# Debug_Module.net
KiCad netlist of a schematic drawn in EAGLE
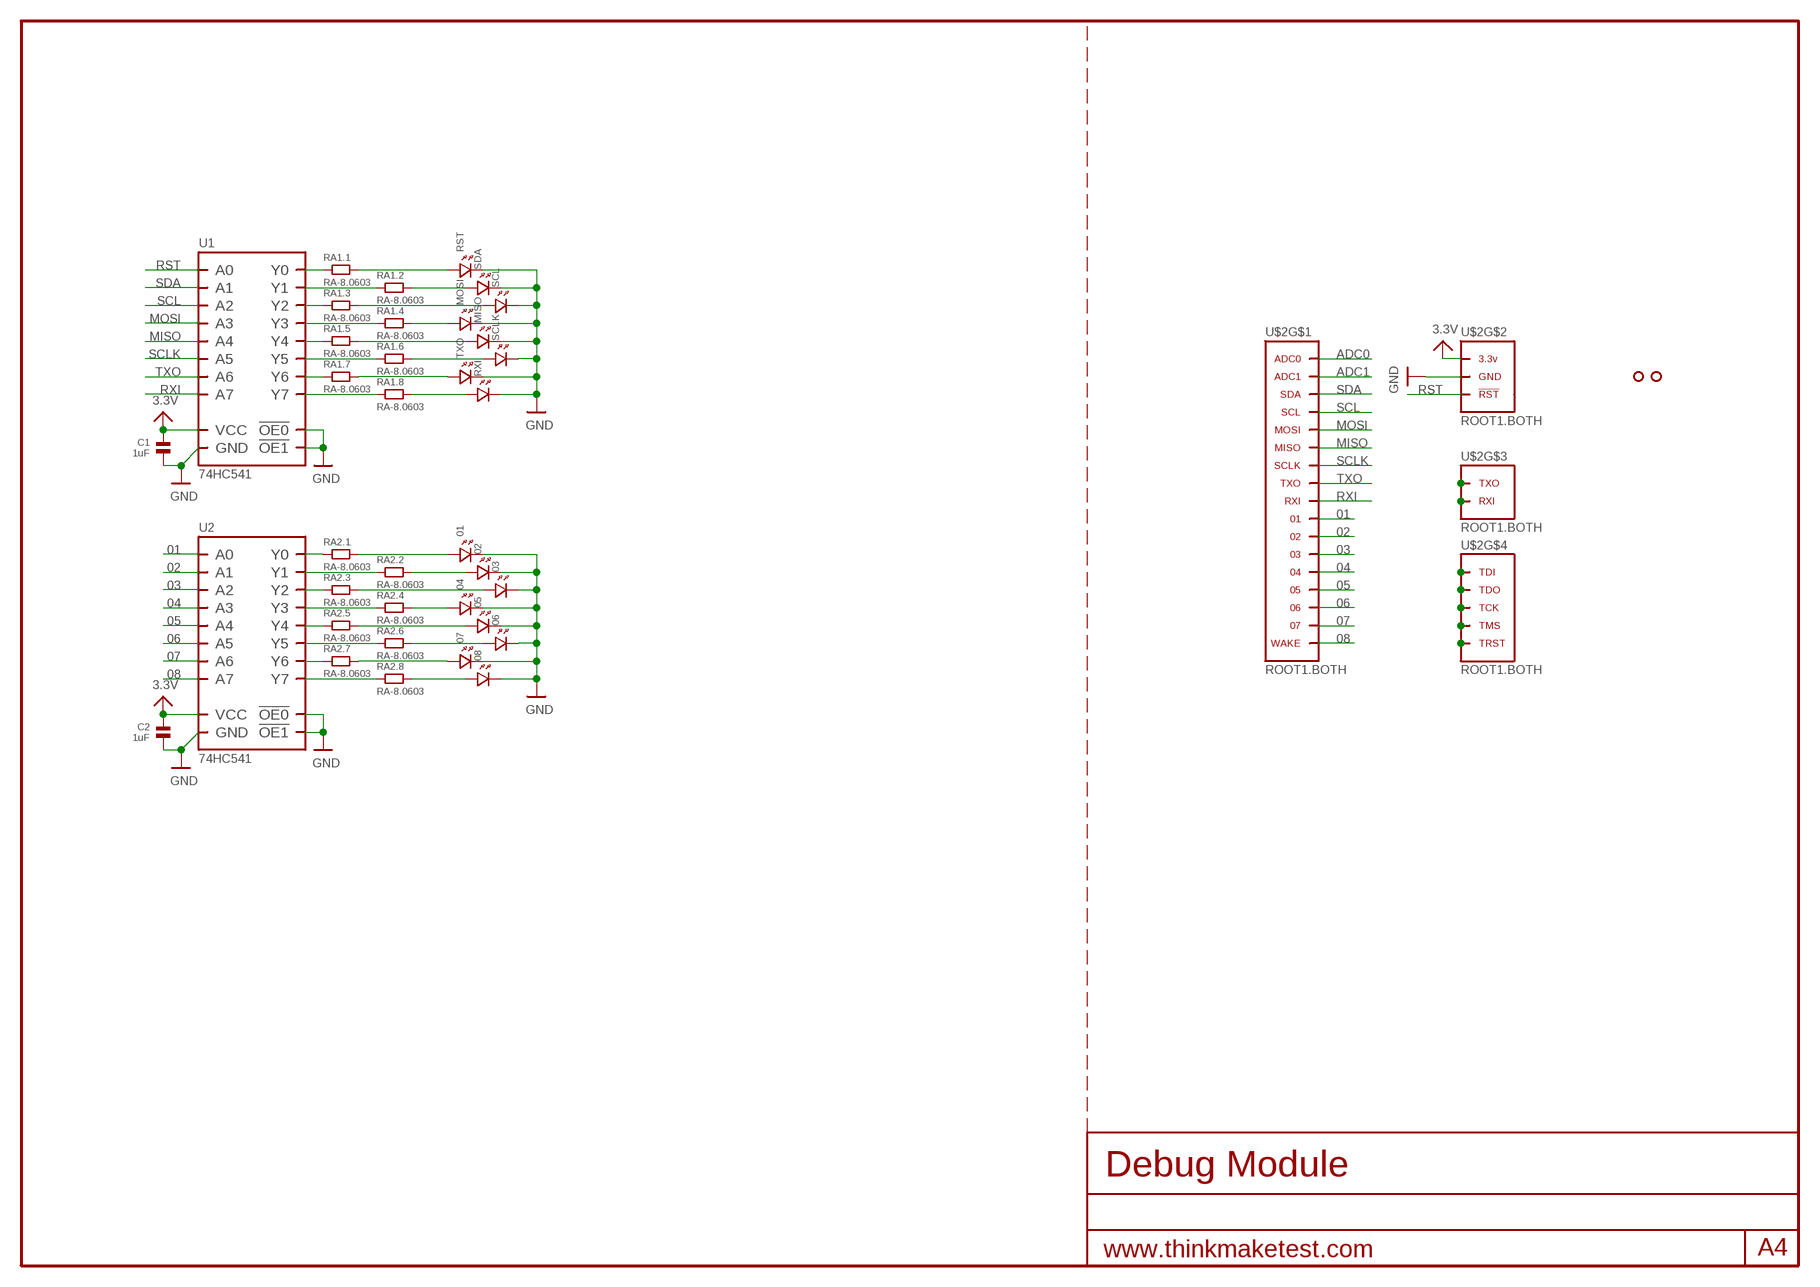
[diagram p0: schematic, sheet 1]

(export (version "E")
  (design (tool "Eeschema 10.0.6"))
  (components
    (comp (ref "01")
      (value "LED.0603")
      (footprint "eagle-import:0603.LED")
      (libsource (lib "eagle-import") (part "LED.0603"))
    )
    (comp (ref "02")
      (value "LED.0603")
      (footprint "eagle-import:0603.LED")
      (libsource (lib "eagle-import") (part "LED.0603"))
    )
    (comp (ref "03")
      (value "LED.0603")
      (footprint "eagle-import:0603.LED")
      (libsource (lib "eagle-import") (part "LED.0603"))
    )
    (comp (ref "04")
      (value "LED.0603")
      (footprint "eagle-import:0603.LED")
      (libsource (lib "eagle-import") (part "LED.0603"))
    )
    (comp (ref "05")
      (value "LED.0603")
      (footprint "eagle-import:0603.LED")
      (libsource (lib "eagle-import") (part "LED.0603"))
    )
    (comp (ref "06")
      (value "LED.0603")
      (footprint "eagle-import:0603.LED")
      (libsource (lib "eagle-import") (part "LED.0603"))
    )
    (comp (ref "07")
      (value "LED.0603")
      (footprint "eagle-import:0603.LED")
      (libsource (lib "eagle-import") (part "LED.0603"))
    )
    (comp (ref "08")
      (value "LED.0603")
      (footprint "eagle-import:0603.LED")
      (libsource (lib "eagle-import") (part "LED.0603"))
    )
    (comp (ref "C1")
      (value "1uF")
      (footprint "eagle-import:0603")
      (libsource (lib "eagle-import") (part "CAPACITOR.0603"))
    )
    (comp (ref "C2")
      (value "1uF")
      (footprint "eagle-import:0603")
      (libsource (lib "eagle-import") (part "CAPACITOR.0603"))
    )
    (comp (ref "MISO")
      (value "LED.0603")
      (footprint "eagle-import:0603.LED")
      (libsource (lib "eagle-import") (part "LED.0603"))
    )
    (comp (ref "MOSI")
      (value "LED.0603")
      (footprint "eagle-import:0603.LED")
      (libsource (lib "eagle-import") (part "LED.0603"))
    )
    (comp (ref "RA1")
      (value "RA-8.0603")
      (footprint "eagle-import:0603.8.C")
      (libsource (lib "eagle-import") (part "RA-8.0603"))
    )
    (comp (ref "RA2")
      (value "RA-8.0603")
      (footprint "eagle-import:0603.8.C")
      (libsource (lib "eagle-import") (part "RA-8.0603"))
    )
    (comp (ref "RST")
      (value "LED.0603")
      (footprint "eagle-import:0603.LED")
      (libsource (lib "eagle-import") (part "LED.0603"))
    )
    (comp (ref "RXI")
      (value "LED.0603")
      (footprint "eagle-import:0603.LED")
      (libsource (lib "eagle-import") (part "LED.0603"))
    )
    (comp (ref "SCL")
      (value "LED.0603")
      (footprint "eagle-import:0603.LED")
      (libsource (lib "eagle-import") (part "LED.0603"))
    )
    (comp (ref "SCLK")
      (value "LED.0603")
      (footprint "eagle-import:0603.LED")
      (libsource (lib "eagle-import") (part "LED.0603"))
    )
    (comp (ref "SDA")
      (value "LED.0603")
      (footprint "eagle-import:0603.LED")
      (libsource (lib "eagle-import") (part "LED.0603"))
    )
    (comp (ref "TXO")
      (value "LED.0603")
      (footprint "eagle-import:0603.LED")
      (libsource (lib "eagle-import") (part "LED.0603"))
    )
    (comp (ref "U$2")
      (value "ROOT1.BOTH")
      (footprint "eagle-import:ROOT1.BOTH")
      (libsource (lib "eagle-import") (part "ROOT1.BOTH"))
    )
    (comp (ref "U$3")
      (value "HOLE.2MM")
      (footprint "eagle-import:2MM")
      (libsource (lib "eagle-import") (part "HOLE.2MM"))
    )
    (comp (ref "U$4")
      (value "HOLE.2MM")
      (footprint "eagle-import:2MM")
      (libsource (lib "eagle-import") (part "HOLE.2MM"))
    )
    (comp (ref "U1")
      (value "74HC541")
      (footprint "eagle-import:DHVQFN20")
      (libsource (lib "eagle-import") (part "74HC541"))
    )
    (comp (ref "U2")
      (value "74HC541")
      (footprint "eagle-import:DHVQFN20")
      (libsource (lib "eagle-import") (part "74HC541"))
    )
  )
  (nets
    (net (code "1") (name "/01") (class "Default")
      (node (ref "U$2") (pin "01") (pinfunction "01_01") (pintype "bidirectional"))
      (node (ref "U$2") (pin "01@1") (pinfunction "01_01@1") (pintype "bidirectional"))
      (node (ref "U$2") (pin "01@VIA") (pinfunction "01_01@VIA") (pintype "bidirectional"))
      (node (ref "U2") (pin "2") (pinfunction "A0_2") (pintype "bidirectional"))
    )
    (net (code "2") (name "/02") (class "Default")
      (node (ref "U$2") (pin "02") (pinfunction "02_02") (pintype "bidirectional"))
      (node (ref "U$2") (pin "02@1") (pinfunction "02_02@1") (pintype "bidirectional"))
      (node (ref "U$2") (pin "02@VIA") (pinfunction "02_02@VIA") (pintype "bidirectional"))
      (node (ref "U2") (pin "3") (pinfunction "A1_3") (pintype "bidirectional"))
    )
    (net (code "3") (name "/03") (class "Default")
      (node (ref "U$2") (pin "03") (pinfunction "03_03") (pintype "bidirectional"))
      (node (ref "U$2") (pin "03@1") (pinfunction "03_03@1") (pintype "bidirectional"))
      (node (ref "U$2") (pin "03@VIA") (pinfunction "03_03@VIA") (pintype "bidirectional"))
      (node (ref "U2") (pin "4") (pinfunction "A2_4") (pintype "bidirectional"))
    )
    (net (code "4") (name "/04") (class "Default")
      (node (ref "U$2") (pin "04") (pinfunction "04_04") (pintype "bidirectional"))
      (node (ref "U$2") (pin "04@1") (pinfunction "04_04@1") (pintype "bidirectional"))
      (node (ref "U$2") (pin "04@VIA") (pinfunction "04_04@VIA") (pintype "bidirectional"))
      (node (ref "U2") (pin "5") (pinfunction "A3_5") (pintype "bidirectional"))
    )
    (net (code "5") (name "/05") (class "Default")
      (node (ref "U$2") (pin "05") (pinfunction "05_05") (pintype "bidirectional"))
      (node (ref "U$2") (pin "05@1") (pinfunction "05_05@1") (pintype "bidirectional"))
      (node (ref "U$2") (pin "05@VIA") (pinfunction "05_05@VIA") (pintype "bidirectional"))
      (node (ref "U2") (pin "6") (pinfunction "A4_6") (pintype "bidirectional"))
    )
    (net (code "6") (name "/06") (class "Default")
      (node (ref "U$2") (pin "06") (pinfunction "06_06") (pintype "bidirectional"))
      (node (ref "U$2") (pin "06@1") (pinfunction "06_06@1") (pintype "bidirectional"))
      (node (ref "U$2") (pin "06@VIA") (pinfunction "06_06@VIA") (pintype "bidirectional"))
      (node (ref "U2") (pin "7") (pinfunction "A5_7") (pintype "bidirectional"))
    )
    (net (code "7") (name "/07") (class "Default")
      (node (ref "U$2") (pin "07") (pinfunction "07_07") (pintype "bidirectional"))
      (node (ref "U$2") (pin "07@1") (pinfunction "07_07@1") (pintype "bidirectional"))
      (node (ref "U$2") (pin "07@VIA") (pinfunction "07_07@VIA") (pintype "bidirectional"))
      (node (ref "U2") (pin "8") (pinfunction "A6_8") (pintype "bidirectional"))
    )
    (net (code "8") (name "/08") (class "Default")
      (node (ref "U$2") (pin "WAKE") (pinfunction "WAKE_WAKE") (pintype "bidirectional"))
      (node (ref "U$2") (pin "WAKE@1") (pinfunction "WAKE_WAKE@1") (pintype "bidirectional"))
      (node (ref "U$2") (pin "WAKE@VIA") (pinfunction "WAKE_WAKE@VIA") (pintype "bidirectional"))
      (node (ref "U2") (pin "9") (pinfunction "A7_9") (pintype "bidirectional"))
    )
    (net (code "9") (name "/ADC0") (class "Default")
      (node (ref "U$2") (pin "ADC0") (pinfunction "ADC0_ADC0") (pintype "bidirectional"))
      (node (ref "U$2") (pin "ADC0@1") (pinfunction "ADC0_ADC0@1") (pintype "bidirectional"))
      (node (ref "U$2") (pin "ADC0@VIA") (pinfunction "ADC0_ADC0@VIA") (pintype "bidirectional"))
    )
    (net (code "10") (name "/ADC1") (class "Default")
      (node (ref "U$2") (pin "ADC1") (pinfunction "ADC1_ADC1") (pintype "bidirectional"))
      (node (ref "U$2") (pin "ADC1@1") (pinfunction "ADC1_ADC1@1") (pintype "bidirectional"))
      (node (ref "U$2") (pin "ADC1@VIA") (pinfunction "ADC1_ADC1@VIA") (pintype "bidirectional"))
    )
    (net (code "11") (name "/MISO") (class "Default")
      (node (ref "U$2") (pin "MISO") (pinfunction "MISO_MISO") (pintype "bidirectional"))
      (node (ref "U$2") (pin "MISO@1") (pinfunction "MISO_MISO@1") (pintype "bidirectional"))
      (node (ref "U$2") (pin "MISO@VIA") (pinfunction "MISO_MISO@VIA") (pintype "bidirectional"))
      (node (ref "U1") (pin "6") (pinfunction "A4_6") (pintype "bidirectional"))
    )
    (net (code "12") (name "/MOSI") (class "Default")
      (node (ref "U$2") (pin "MOSI") (pinfunction "MOSI_MOSI") (pintype "bidirectional"))
      (node (ref "U$2") (pin "MOSI@1") (pinfunction "MOSI_MOSI@1") (pintype "bidirectional"))
      (node (ref "U$2") (pin "MOSI@VIA") (pinfunction "MOSI_MOSI@VIA") (pintype "bidirectional"))
      (node (ref "U1") (pin "5") (pinfunction "A3_5") (pintype "bidirectional"))
    )
    (net (code "13") (name "/RST") (class "Default")
      (node (ref "U$2") (pin "RST") (pinfunction "~{RST}_RST") (pintype "bidirectional"))
      (node (ref "U$2") (pin "RST@1") (pinfunction "~{RST}_RST@1") (pintype "bidirectional"))
      (node (ref "U$2") (pin "RST@VIA") (pinfunction "~{RST}_RST@VIA") (pintype "bidirectional"))
      (node (ref "U1") (pin "2") (pinfunction "A0_2") (pintype "bidirectional"))
    )
    (net (code "14") (name "/RXI") (class "Default")
      (node (ref "U$2") (pin "RXI") (pinfunction "RXI_RXI") (pintype "bidirectional"))
      (node (ref "U$2") (pin "RXI@1") (pinfunction "RXI_RXI@1") (pintype "bidirectional"))
      (node (ref "U$2") (pin "RXI@VIA") (pinfunction "RXI_RXI@VIA") (pintype "bidirectional"))
      (node (ref "U1") (pin "9") (pinfunction "A7_9") (pintype "bidirectional"))
    )
    (net (code "15") (name "/SCL") (class "Default")
      (node (ref "U$2") (pin "SCL") (pinfunction "SCL_SCL") (pintype "bidirectional"))
      (node (ref "U$2") (pin "SCL@1") (pinfunction "SCL_SCL@1") (pintype "bidirectional"))
      (node (ref "U$2") (pin "SCL@VIA") (pinfunction "SCL_SCL@VIA") (pintype "bidirectional"))
      (node (ref "U1") (pin "4") (pinfunction "A2_4") (pintype "bidirectional"))
    )
    (net (code "16") (name "/SCLK") (class "Default")
      (node (ref "U$2") (pin "SCLK") (pinfunction "SCLK_SCLK") (pintype "bidirectional"))
      (node (ref "U$2") (pin "SCLK@1") (pinfunction "SCLK_SCLK@1") (pintype "bidirectional"))
      (node (ref "U$2") (pin "SCLK@VIA") (pinfunction "SCLK_SCLK@VIA") (pintype "bidirectional"))
      (node (ref "U1") (pin "7") (pinfunction "A5_7") (pintype "bidirectional"))
    )
    (net (code "17") (name "/SDA") (class "Default")
      (node (ref "U$2") (pin "SDA") (pinfunction "SDA_SDA") (pintype "bidirectional"))
      (node (ref "U$2") (pin "SDA@1") (pinfunction "SDA_SDA@1") (pintype "bidirectional"))
      (node (ref "U$2") (pin "SDA@VIA") (pinfunction "SDA_SDA@VIA") (pintype "bidirectional"))
      (node (ref "U1") (pin "3") (pinfunction "A1_3") (pintype "bidirectional"))
    )
    (net (code "18") (name "/TXO") (class "Default")
      (node (ref "U$2") (pin "TXO") (pinfunction "TXO_TXO") (pintype "bidirectional"))
      (node (ref "U$2") (pin "TXO@1") (pinfunction "TXO_TXO@1") (pintype "bidirectional"))
      (node (ref "U$2") (pin "TXO@VIA") (pinfunction "TXO_TXO@VIA") (pintype "bidirectional"))
      (node (ref "U1") (pin "8") (pinfunction "A6_8") (pintype "bidirectional"))
    )
    (net (code "19") (name "3.3V") (class "Default")
      (node (ref "C1") (pin "1") (pinfunction "1_1") (pintype "bidirectional"))
      (node (ref "C2") (pin "1") (pinfunction "1_1") (pintype "bidirectional"))
      (node (ref "U$2") (pin "3.3V@1") (pinfunction "3.3V_3.3V@1") (pintype "bidirectional"))
      (node (ref "U$2") (pin "3.3V@10") (pinfunction "3.3V_3.3V@10") (pintype "bidirectional"))
      (node (ref "U$2") (pin "3.3V@11") (pinfunction "3.3V_3.3V@11") (pintype "bidirectional"))
      (node (ref "U$2") (pin "3.3V@12") (pinfunction "3.3V_3.3V@12") (pintype "bidirectional"))
      (node (ref "U$2") (pin "3.3V@13") (pinfunction "3.3V_3.3V@13") (pintype "bidirectional"))
      (node (ref "U$2") (pin "3.3V@14") (pinfunction "3.3V_3.3V@14") (pintype "bidirectional"))
      (node (ref "U$2") (pin "3.3V@15") (pinfunction "3.3V_3.3V@15") (pintype "bidirectional"))
      (node (ref "U$2") (pin "3.3V@16") (pinfunction "3.3V_3.3V@16") (pintype "bidirectional"))
      (node (ref "U$2") (pin "3.3V@17") (pinfunction "3.3V_3.3V@17") (pintype "bidirectional"))
      (node (ref "U$2") (pin "3.3V@18") (pinfunction "3.3V_3.3V@18") (pintype "bidirectional"))
      (node (ref "U$2") (pin "3.3V@19") (pinfunction "3.3V_3.3V@19") (pintype "bidirectional"))
      (node (ref "U$2") (pin "3.3V@2") (pinfunction "3.3V_3.3V@2") (pintype "bidirectional"))
      (node (ref "U$2") (pin "3.3V@20") (pinfunction "3.3V_3.3V@20") (pintype "bidirectional"))
      (node (ref "U$2") (pin "3.3V@21") (pinfunction "3.3V_3.3V@21") (pintype "bidirectional"))
      (node (ref "U$2") (pin "3.3V@22") (pinfunction "3.3V_3.3V@22") (pintype "bidirectional"))
      (node (ref "U$2") (pin "3.3V@23") (pinfunction "3.3V_3.3V@23") (pintype "bidirectional"))
      (node (ref "U$2") (pin "3.3V@24") (pinfunction "3.3V_3.3V@24") (pintype "bidirectional"))
      (node (ref "U$2") (pin "3.3V@3") (pinfunction "3.3V_3.3V@3") (pintype "bidirectional"))
      (node (ref "U$2") (pin "3.3V@4") (pinfunction "3.3V_3.3V@4") (pintype "bidirectional"))
      (node (ref "U$2") (pin "3.3V@5") (pinfunction "3.3V_3.3V@5") (pintype "bidirectional"))
      (node (ref "U$2") (pin "3.3V@6") (pinfunction "3.3V_3.3V@6") (pintype "bidirectional"))
      (node (ref "U$2") (pin "3.3V@7") (pinfunction "3.3V_3.3V@7") (pintype "bidirectional"))
      (node (ref "U$2") (pin "3.3V@8") (pinfunction "3.3V_3.3V@8") (pintype "bidirectional"))
      (node (ref "U$2") (pin "3.3V@9") (pinfunction "3.3V_3.3V@9") (pintype "bidirectional"))
      (node (ref "U$2") (pin "3.3V@VIA") (pinfunction "3.3V_3.3V@VIA") (pintype "bidirectional"))
      (node (ref "U1") (pin "20") (pinfunction "VCC_20") (pintype "bidirectional"))
      (node (ref "U2") (pin "20") (pinfunction "VCC_20") (pintype "bidirectional"))
    )
    (net (code "20") (name "GND") (class "Default")
      (node (ref "01") (pin "P$2") (pinfunction "2_P$2") (pintype "bidirectional"))
      (node (ref "02") (pin "P$2") (pinfunction "2_P$2") (pintype "bidirectional"))
      (node (ref "03") (pin "P$2") (pinfunction "2_P$2") (pintype "bidirectional"))
      (node (ref "04") (pin "P$2") (pinfunction "2_P$2") (pintype "bidirectional"))
      (node (ref "05") (pin "P$2") (pinfunction "2_P$2") (pintype "bidirectional"))
      (node (ref "06") (pin "P$2") (pinfunction "2_P$2") (pintype "bidirectional"))
      (node (ref "07") (pin "P$2") (pinfunction "2_P$2") (pintype "bidirectional"))
      (node (ref "08") (pin "P$2") (pinfunction "2_P$2") (pintype "bidirectional"))
      (node (ref "C1") (pin "2") (pinfunction "2_2") (pintype "bidirectional"))
      (node (ref "C2") (pin "2") (pinfunction "2_2") (pintype "bidirectional"))
      (node (ref "MISO") (pin "P$2") (pinfunction "2_P$2") (pintype "bidirectional"))
      (node (ref "MOSI") (pin "P$2") (pinfunction "2_P$2") (pintype "bidirectional"))
      (node (ref "RST") (pin "P$2") (pinfunction "2_P$2") (pintype "bidirectional"))
      (node (ref "RXI") (pin "P$2") (pinfunction "2_P$2") (pintype "bidirectional"))
      (node (ref "SCL") (pin "P$2") (pinfunction "2_P$2") (pintype "bidirectional"))
      (node (ref "SCLK") (pin "P$2") (pinfunction "2_P$2") (pintype "bidirectional"))
      (node (ref "SDA") (pin "P$2") (pinfunction "2_P$2") (pintype "bidirectional"))
      (node (ref "TXO") (pin "P$2") (pinfunction "2_P$2") (pintype "bidirectional"))
      (node (ref "U$2") (pin "GND@1") (pinfunction "GND_GND@1") (pintype "bidirectional"))
      (node (ref "U$2") (pin "GND@10") (pinfunction "GND_GND@10") (pintype "bidirectional"))
      (node (ref "U$2") (pin "GND@11") (pinfunction "GND_GND@11") (pintype "bidirectional"))
      (node (ref "U$2") (pin "GND@12") (pinfunction "GND_GND@12") (pintype "bidirectional"))
      (node (ref "U$2") (pin "GND@13") (pinfunction "GND_GND@13") (pintype "bidirectional"))
      (node (ref "U$2") (pin "GND@14") (pinfunction "GND_GND@14") (pintype "bidirectional"))
      (node (ref "U$2") (pin "GND@15") (pinfunction "GND_GND@15") (pintype "bidirectional"))
      (node (ref "U$2") (pin "GND@16") (pinfunction "GND_GND@16") (pintype "bidirectional"))
      (node (ref "U$2") (pin "GND@17") (pinfunction "GND_GND@17") (pintype "bidirectional"))
      (node (ref "U$2") (pin "GND@18") (pinfunction "GND_GND@18") (pintype "bidirectional"))
      (node (ref "U$2") (pin "GND@19") (pinfunction "GND_GND@19") (pintype "bidirectional"))
      (node (ref "U$2") (pin "GND@2") (pinfunction "GND_GND@2") (pintype "bidirectional"))
      (node (ref "U$2") (pin "GND@20") (pinfunction "GND_GND@20") (pintype "bidirectional"))
      (node (ref "U$2") (pin "GND@21") (pinfunction "GND_GND@21") (pintype "bidirectional"))
      (node (ref "U$2") (pin "GND@22") (pinfunction "GND_GND@22") (pintype "bidirectional"))
      (node (ref "U$2") (pin "GND@23") (pinfunction "GND_GND@23") (pintype "bidirectional"))
      (node (ref "U$2") (pin "GND@24") (pinfunction "GND_GND@24") (pintype "bidirectional"))
      (node (ref "U$2") (pin "GND@25") (pinfunction "GND_GND@25") (pintype "bidirectional"))
      (node (ref "U$2") (pin "GND@26") (pinfunction "GND_GND@26") (pintype "bidirectional"))
      (node (ref "U$2") (pin "GND@3") (pinfunction "GND_GND@3") (pintype "bidirectional"))
      (node (ref "U$2") (pin "GND@4") (pinfunction "GND_GND@4") (pintype "bidirectional"))
      (node (ref "U$2") (pin "GND@5") (pinfunction "GND_GND@5") (pintype "bidirectional"))
      (node (ref "U$2") (pin "GND@6") (pinfunction "GND_GND@6") (pintype "bidirectional"))
      (node (ref "U$2") (pin "GND@7") (pinfunction "GND_GND@7") (pintype "bidirectional"))
      (node (ref "U$2") (pin "GND@8") (pinfunction "GND_GND@8") (pintype "bidirectional"))
      (node (ref "U$2") (pin "GND@9") (pinfunction "GND_GND@9") (pintype "bidirectional"))
      (node (ref "U$2") (pin "GND@VIA") (pinfunction "GND_GND@VIA") (pintype "bidirectional"))
      (node (ref "U1") (pin "1") (pinfunction "~{OE0}_1") (pintype "bidirectional"))
      (node (ref "U1") (pin "10") (pinfunction "GND_10") (pintype "bidirectional"))
      (node (ref "U1") (pin "19") (pinfunction "~{OE1}_19") (pintype "bidirectional"))
      (node (ref "U1") (pin "PAD") (pinfunction "GND_PAD") (pintype "bidirectional"))
      (node (ref "U2") (pin "1") (pinfunction "~{OE0}_1") (pintype "bidirectional"))
      (node (ref "U2") (pin "10") (pinfunction "GND_10") (pintype "bidirectional"))
      (node (ref "U2") (pin "19") (pinfunction "~{OE1}_19") (pintype "bidirectional"))
      (node (ref "U2") (pin "PAD") (pinfunction "GND_PAD") (pintype "bidirectional"))
    )
    (net (code "21") (name "Net-(01-1)") (class "Default")
      (node (ref "01") (pin "P$1") (pinfunction "1_P$1") (pintype "bidirectional"))
      (node (ref "RA2") (pin "2") (pinfunction "2_2") (pintype "bidirectional"))
    )
    (net (code "22") (name "Net-(02-1)") (class "Default")
      (node (ref "02") (pin "P$1") (pinfunction "1_P$1") (pintype "bidirectional"))
      (node (ref "RA2") (pin "4") (pinfunction "2_4") (pintype "bidirectional"))
    )
    (net (code "23") (name "Net-(03-1)") (class "Default")
      (node (ref "03") (pin "P$1") (pinfunction "1_P$1") (pintype "bidirectional"))
      (node (ref "RA2") (pin "6") (pinfunction "2_6") (pintype "bidirectional"))
    )
    (net (code "24") (name "Net-(04-1)") (class "Default")
      (node (ref "04") (pin "P$1") (pinfunction "1_P$1") (pintype "bidirectional"))
      (node (ref "RA2") (pin "8") (pinfunction "2_8") (pintype "bidirectional"))
    )
    (net (code "25") (name "Net-(05-1)") (class "Default")
      (node (ref "05") (pin "P$1") (pinfunction "1_P$1") (pintype "bidirectional"))
      (node (ref "RA2") (pin "10") (pinfunction "2_10") (pintype "bidirectional"))
    )
    (net (code "26") (name "Net-(06-1)") (class "Default")
      (node (ref "06") (pin "P$1") (pinfunction "1_P$1") (pintype "bidirectional"))
      (node (ref "RA2") (pin "12") (pinfunction "2_12") (pintype "bidirectional"))
    )
    (net (code "27") (name "Net-(07-1)") (class "Default")
      (node (ref "07") (pin "P$1") (pinfunction "1_P$1") (pintype "bidirectional"))
      (node (ref "RA2") (pin "14") (pinfunction "2_14") (pintype "bidirectional"))
    )
    (net (code "28") (name "Net-(08-1)") (class "Default")
      (node (ref "08") (pin "P$1") (pinfunction "1_P$1") (pintype "bidirectional"))
      (node (ref "RA2") (pin "16") (pinfunction "2_16") (pintype "bidirectional"))
    )
    (net (code "29") (name "Net-(MISO-1)") (class "Default")
      (node (ref "MISO") (pin "P$1") (pinfunction "1_P$1") (pintype "bidirectional"))
      (node (ref "RA1") (pin "10") (pinfunction "2_10") (pintype "bidirectional"))
    )
    (net (code "30") (name "Net-(MOSI-1)") (class "Default")
      (node (ref "MOSI") (pin "P$1") (pinfunction "1_P$1") (pintype "bidirectional"))
      (node (ref "RA1") (pin "8") (pinfunction "2_8") (pintype "bidirectional"))
    )
    (net (code "31") (name "Net-(RA1B-1)") (class "Default")
      (node (ref "RA1") (pin "3") (pinfunction "1_3") (pintype "bidirectional"))
      (node (ref "U1") (pin "17") (pinfunction "Y1_17") (pintype "bidirectional"))
    )
    (net (code "32") (name "Net-(RA1B-2)") (class "Default")
      (node (ref "RA1") (pin "4") (pinfunction "2_4") (pintype "bidirectional"))
      (node (ref "SDA") (pin "P$1") (pinfunction "1_P$1") (pintype "bidirectional"))
    )
    (net (code "33") (name "Net-(RA1C-1)") (class "Default")
      (node (ref "RA1") (pin "5") (pinfunction "1_5") (pintype "bidirectional"))
      (node (ref "U1") (pin "16") (pinfunction "Y2_16") (pintype "bidirectional"))
    )
    (net (code "34") (name "Net-(RA1C-2)") (class "Default")
      (node (ref "RA1") (pin "6") (pinfunction "2_6") (pintype "bidirectional"))
      (node (ref "SCL") (pin "P$1") (pinfunction "1_P$1") (pintype "bidirectional"))
    )
    (net (code "35") (name "Net-(RA1D-1)") (class "Default")
      (node (ref "RA1") (pin "7") (pinfunction "1_7") (pintype "bidirectional"))
      (node (ref "U1") (pin "15") (pinfunction "Y3_15") (pintype "bidirectional"))
    )
    (net (code "36") (name "Net-(RA1E-1)") (class "Default")
      (node (ref "RA1") (pin "9") (pinfunction "1_9") (pintype "bidirectional"))
      (node (ref "U1") (pin "14") (pinfunction "Y4_14") (pintype "bidirectional"))
    )
    (net (code "37") (name "Net-(RA1F-1)") (class "Default")
      (node (ref "RA1") (pin "11") (pinfunction "1_11") (pintype "bidirectional"))
      (node (ref "U1") (pin "13") (pinfunction "Y5_13") (pintype "bidirectional"))
    )
    (net (code "38") (name "Net-(RA1F-2)") (class "Default")
      (node (ref "RA1") (pin "12") (pinfunction "2_12") (pintype "bidirectional"))
      (node (ref "SCLK") (pin "P$1") (pinfunction "1_P$1") (pintype "bidirectional"))
    )
    (net (code "39") (name "Net-(RA1G-1)") (class "Default")
      (node (ref "RA1") (pin "13") (pinfunction "1_13") (pintype "bidirectional"))
      (node (ref "U1") (pin "12") (pinfunction "Y6_12") (pintype "bidirectional"))
    )
    (net (code "40") (name "Net-(RA1G-2)") (class "Default")
      (node (ref "RA1") (pin "14") (pinfunction "2_14") (pintype "bidirectional"))
      (node (ref "TXO") (pin "P$1") (pinfunction "1_P$1") (pintype "bidirectional"))
    )
    (net (code "41") (name "Net-(RA1H-1)") (class "Default")
      (node (ref "RA1") (pin "15") (pinfunction "1_15") (pintype "bidirectional"))
      (node (ref "U1") (pin "11") (pinfunction "Y7_11") (pintype "bidirectional"))
    )
    (net (code "42") (name "Net-(RA1H-2)") (class "Default")
      (node (ref "RA1") (pin "16") (pinfunction "2_16") (pintype "bidirectional"))
      (node (ref "RXI") (pin "P$1") (pinfunction "1_P$1") (pintype "bidirectional"))
    )
    (net (code "43") (name "Net-(RA2B-1)") (class "Default")
      (node (ref "RA2") (pin "3") (pinfunction "1_3") (pintype "bidirectional"))
      (node (ref "U2") (pin "17") (pinfunction "Y1_17") (pintype "bidirectional"))
    )
    (net (code "44") (name "Net-(RA2C-1)") (class "Default")
      (node (ref "RA2") (pin "5") (pinfunction "1_5") (pintype "bidirectional"))
      (node (ref "U2") (pin "16") (pinfunction "Y2_16") (pintype "bidirectional"))
    )
    (net (code "45") (name "Net-(RA2D-1)") (class "Default")
      (node (ref "RA2") (pin "7") (pinfunction "1_7") (pintype "bidirectional"))
      (node (ref "U2") (pin "15") (pinfunction "Y3_15") (pintype "bidirectional"))
    )
    (net (code "46") (name "Net-(RA2E-1)") (class "Default")
      (node (ref "RA2") (pin "9") (pinfunction "1_9") (pintype "bidirectional"))
      (node (ref "U2") (pin "14") (pinfunction "Y4_14") (pintype "bidirectional"))
    )
    (net (code "47") (name "Net-(RA2F-1)") (class "Default")
      (node (ref "RA2") (pin "11") (pinfunction "1_11") (pintype "bidirectional"))
      (node (ref "U2") (pin "13") (pinfunction "Y5_13") (pintype "bidirectional"))
    )
    (net (code "48") (name "Net-(RA2G-1)") (class "Default")
      (node (ref "RA2") (pin "13") (pinfunction "1_13") (pintype "bidirectional"))
      (node (ref "U2") (pin "12") (pinfunction "Y6_12") (pintype "bidirectional"))
    )
    (net (code "49") (name "Net-(RA2H-1)") (class "Default")
      (node (ref "RA2") (pin "15") (pinfunction "1_15") (pintype "bidirectional"))
      (node (ref "U2") (pin "11") (pinfunction "Y7_11") (pintype "bidirectional"))
    )
    (net (code "50") (name "Net-(RST-1)") (class "Default")
      (node (ref "RA1") (pin "2") (pinfunction "2_2") (pintype "bidirectional"))
      (node (ref "RST") (pin "P$1") (pinfunction "1_P$1") (pintype "bidirectional"))
    )
    (net (code "51") (name "Net-(U$2-PadTCK)") (class "Default")
      (node (ref "U$2") (pin "TCK") (pinfunction "TCK_TCK") (pintype "bidirectional"))
      (node (ref "U$2") (pin "TCK@1") (pinfunction "TCK_TCK@1") (pintype "bidirectional"))
      (node (ref "U$2") (pin "TCK@VIA") (pinfunction "TCK_TCK@VIA") (pintype "bidirectional"))
    )
    (net (code "52") (name "Net-(U$2-PadTDI)") (class "Default")
      (node (ref "U$2") (pin "TDI") (pinfunction "TDI_TDI") (pintype "bidirectional"))
      (node (ref "U$2") (pin "TDI@1") (pinfunction "TDI_TDI@1") (pintype "bidirectional"))
      (node (ref "U$2") (pin "TDI@VIA") (pinfunction "TDI_TDI@VIA") (pintype "bidirectional"))
    )
    (net (code "53") (name "Net-(U$2-PadTDO)") (class "Default")
      (node (ref "U$2") (pin "TDO") (pinfunction "TDO_TDO") (pintype "bidirectional"))
      (node (ref "U$2") (pin "TDO@1") (pinfunction "TDO_TDO@1") (pintype "bidirectional"))
      (node (ref "U$2") (pin "TDO@VIA") (pinfunction "TDO_TDO@VIA") (pintype "bidirectional"))
    )
    (net (code "54") (name "Net-(U$2-PadTMS)") (class "Default")
      (node (ref "U$2") (pin "TMS") (pinfunction "TMS_TMS") (pintype "bidirectional"))
      (node (ref "U$2") (pin "TMS@1") (pinfunction "TMS_TMS@1") (pintype "bidirectional"))
      (node (ref "U$2") (pin "TMS@VIA") (pinfunction "TMS_TMS@VIA") (pintype "bidirectional"))
    )
    (net (code "55") (name "Net-(U$2-PadTRST)") (class "Default")
      (node (ref "U$2") (pin "TRST") (pinfunction "TRST_TRST") (pintype "bidirectional"))
      (node (ref "U$2") (pin "TRST@1") (pinfunction "TRST_TRST@1") (pintype "bidirectional"))
      (node (ref "U$2") (pin "TRST@VIA") (pinfunction "TRST_TRST@VIA") (pintype "bidirectional"))
    )
    (net (code "56") (name "Net-(U$2C-RXI-PadRXI.DBG)") (class "Default")
      (node (ref "U$2") (pin "RXI.DBG") (pinfunction "RXI_RXI.DBG") (pintype "bidirectional"))
      (node (ref "U$2") (pin "RXI.DBG@1") (pinfunction "RXI_RXI.DBG@1") (pintype "bidirectional"))
      (node (ref "U$2") (pin "RXI.DBG@VIA") (pinfunction "RXI_RXI.DBG@VIA") (pintype "bidirectional"))
    )
    (net (code "57") (name "Net-(U$2C-TXO-PadTXO.DBG)") (class "Default")
      (node (ref "U$2") (pin "TXO.DBG") (pinfunction "TXO_TXO.DBG") (pintype "bidirectional"))
      (node (ref "U$2") (pin "TXO.DBG@1") (pinfunction "TXO_TXO.DBG@1") (pintype "bidirectional"))
      (node (ref "U$2") (pin "TXO.DBG@VIA") (pinfunction "TXO_TXO.DBG@VIA") (pintype "bidirectional"))
    )
    (net (code "58") (name "Net-(U1-Y0)") (class "Default")
      (node (ref "RA1") (pin "1") (pinfunction "1_1") (pintype "bidirectional"))
      (node (ref "U1") (pin "18") (pinfunction "Y0_18") (pintype "bidirectional"))
    )
    (net (code "59") (name "Net-(U2-Y0)") (class "Default")
      (node (ref "RA2") (pin "1") (pinfunction "1_1") (pintype "bidirectional"))
      (node (ref "U2") (pin "18") (pinfunction "Y0_18") (pintype "bidirectional"))
    )
  )
)
